# HDMI.net
KiCad netlist of a schematic drawn in Altium Designer
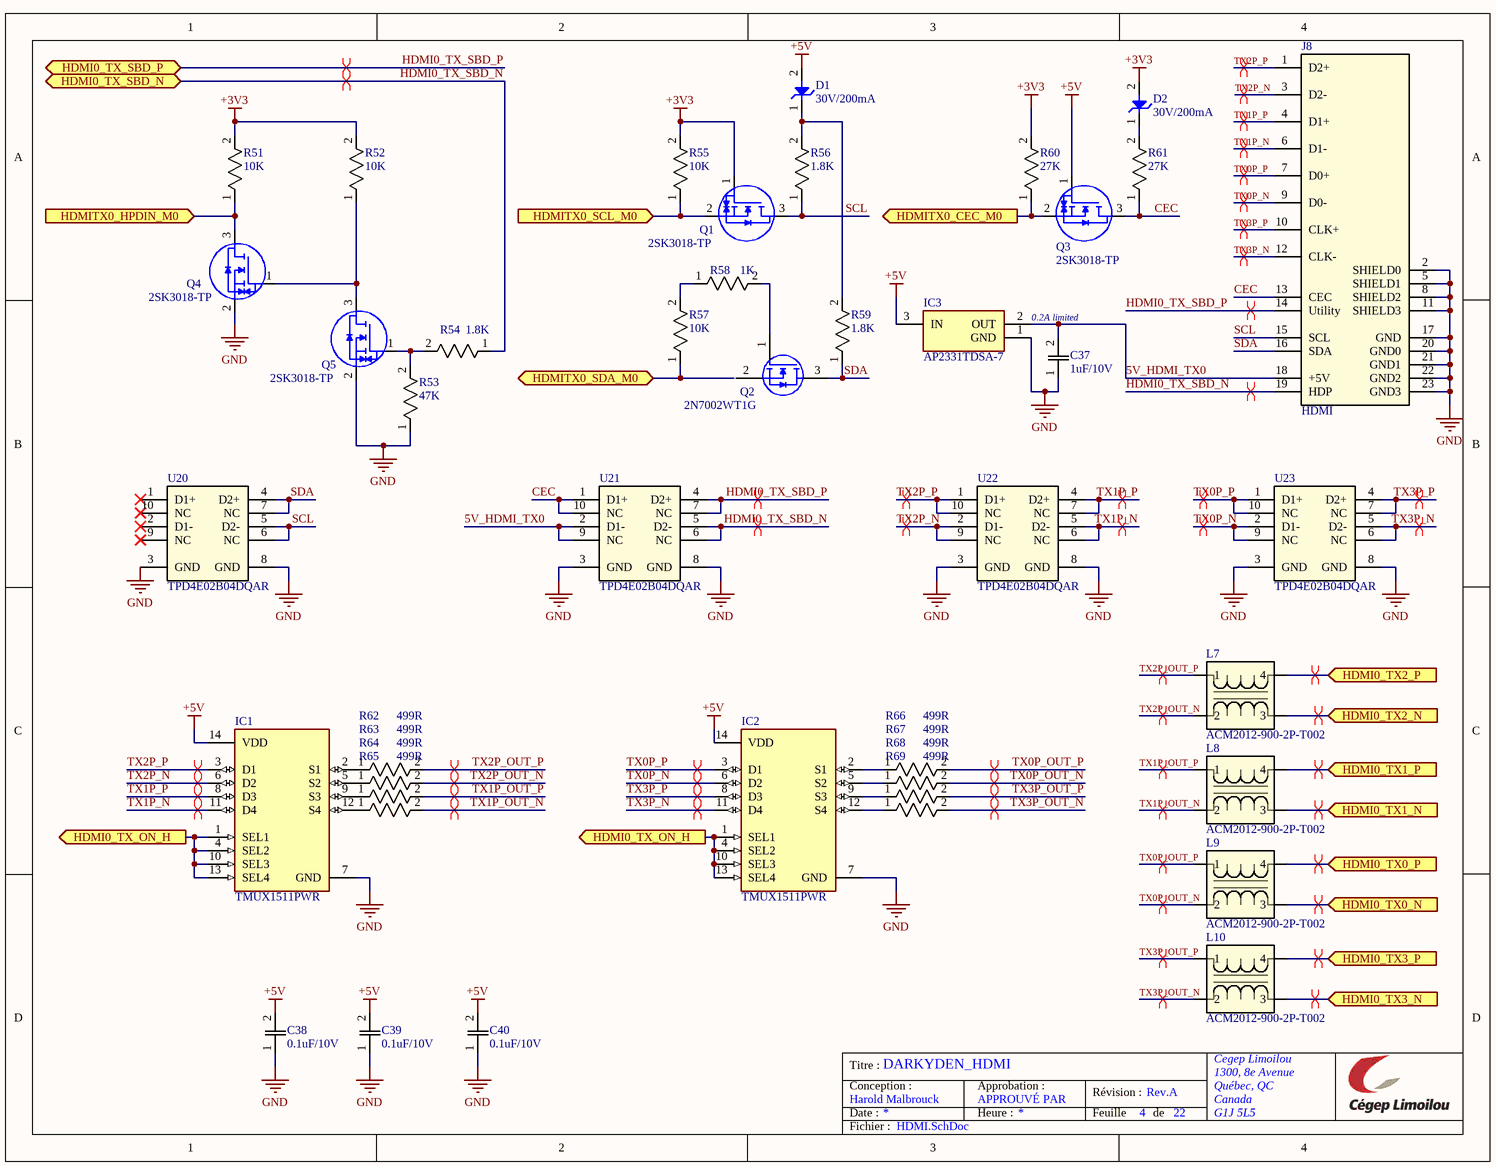
[diagram p0: HDMI.SchDoc]

(export (version "E")
  (design (tool "Eeschema 10.0.6"))
  (components
    (comp (ref "C37")
      (value "1uF/10V")
      (footprint "CAPC220145_88N_KEM")
      (description "Multilayer Ceramic Capacitors MLCC - SMD/SMT 10V 1uF X7R 0805 10%")
      (fields
        (field (name "MANUFACTURER") "KEMET")
        (field (name "MANUFACTURER PART NUMBER") "C0805C105K8RACTU")
      )
      (libsource (lib "C0805C105K8RACTU") (part "C0805C105K8RACTU"))
    )
    (comp (ref "C38")
      (value "0.1uF/10V")
      (footprint "CAPC220145_88N_KEM")
      (description "Cap Ceramic 0.1uF 10V X7R 5% Pad SMD 0805 125C T/R")
      (fields
        (field (name "MANUFACTURER") "KEMET")
        (field (name "MANUFACTURER PART NUMBER") "C0805C104J8RACTU")
      )
      (libsource (lib "C0805C104J8RACTU") (part "C0805C104J8RACTU"))
    )
    (comp (ref "C39")
      (value "0.1uF/10V")
      (footprint "CAPC220145_88N_KEM")
      (description "Cap Ceramic 0.1uF 10V X7R 5% Pad SMD 0805 125C T/R")
      (fields
        (field (name "MANUFACTURER") "KEMET")
        (field (name "MANUFACTURER PART NUMBER") "C0805C104J8RACTU")
      )
      (libsource (lib "C0805C104J8RACTU") (part "C0805C104J8RACTU"))
    )
    (comp (ref "C40")
      (value "0.1uF/10V")
      (footprint "CAPC220145_88N_KEM")
      (description "Cap Ceramic 0.1uF 10V X7R 5% Pad SMD 0805 125C T/R")
      (fields
        (field (name "MANUFACTURER") "KEMET")
        (field (name "MANUFACTURER PART NUMBER") "C0805C104J8RACTU")
      )
      (libsource (lib "C0805C104J8RACTU") (part "C0805C104J8RACTU"))
    )
    (comp (ref "D1")
      (value "30V/200mA")
      (footprint "SamacSys:SODFL1608X70N")
      (description "SCHOTTKY BARRIER DIODE Rectifier Diode, Schottky, 1 Phase, 1 Element, 0.2A, 30V V(RRM), Silicon")
      (fields
        (field (name "MANUFACTURER_PART_NUMBER") "RB521S30T1G")
        (field (name "MOUSER PART NUMBER") "863-RB521S30T1G")
      )
      (libsource (lib "SamacSys") (part "RB521S30T1G"))
    )
    (comp (ref "D2")
      (value "30V/200mA")
      (footprint "SamacSys:SODFL1608X70N")
      (description "SCHOTTKY BARRIER DIODE Rectifier Diode, Schottky, 1 Phase, 1 Element, 0.2A, 30V V(RRM), Silicon")
      (fields
        (field (name "MANUFACTURER_PART_NUMBER") "RB521S30T1G")
        (field (name "MOUSER PART NUMBER") "863-RB521S30T1G")
      )
      (libsource (lib "SamacSys") (part "RB521S30T1G"))
    )
    (comp (ref "IC1")
      (value "TMUX1511PWR")
      (footprint "SamacSys:SOP65P640X120-14N")
      (fields
        (field (name "MOUSER PART NUMBER") "595-TMUX1511PWR")
        (field (name "MANUFACTURER") "Texas Instruments")
      )
      (libsource (lib "SamacSys") (part "TMUX1511PWR"))
    )
    (comp (ref "IC2")
      (value "TMUX1511PWR")
      (footprint "SamacSys:SOP65P640X120-14N")
      (fields
        (field (name "MOUSER PART NUMBER") "595-TMUX1511PWR")
        (field (name "MANUFACTURER") "Texas Instruments")
      )
      (libsource (lib "SamacSys") (part "TMUX1511PWR"))
    )
    (comp (ref "IC3")
      (value "AP2331TDSA-7")
      (footprint "SamacSys:SOT96P240X110-3N")
      (description "USB Power Switch Single 5.2V 0.4A 3-Pin SOT-23 T/R")
      (fields (field (name "MOUSER PART NUMBER") "621-AP2331TDSA-7") (field (name "MANUFACTURER") "Diodes"))
      (libsource (lib "SamacSys") (part "AP2331TDSA-7"))
    )
    (comp (ref "J8")
      (value "HDMI")
      (footprint "CONN19_2001-1-2-21-00-BK_CNC")
      (description "2001-1-2-21-00-BK")
      (libsource (lib "HDMI") (part "HDMI"))
    )
    (comp (ref "L7")
      (value "ACM2012-900-2P-T002")
      (footprint "SamacSys:ACM20129002PT002")
      (description "Ferrite Beads Wirewound Common Mode Filter 90Ohm 100MHz 400mA 0805 T/R")
      (fields (field (name "MOUSER PART NUMBER") "810-ACM20129002PT002") (field (name "MANUFACTURER") "TDK"))
      (libsource (lib "SamacSys") (part "ACM2012-900-2P-T002"))
    )
    (comp (ref "L8")
      (value "ACM2012-900-2P-T002")
      (footprint "SamacSys:ACM20129002PT002")
      (description "Ferrite Beads Wirewound Common Mode Filter 90Ohm 100MHz 400mA 0805 T/R")
      (fields (field (name "MOUSER PART NUMBER") "810-ACM20129002PT002") (field (name "MANUFACTURER") "TDK"))
      (libsource (lib "SamacSys") (part "ACM2012-900-2P-T002"))
    )
    (comp (ref "L9")
      (value "ACM2012-900-2P-T002")
      (footprint "SamacSys:ACM20129002PT002")
      (description "Ferrite Beads Wirewound Common Mode Filter 90Ohm 100MHz 400mA 0805 T/R")
      (fields (field (name "MOUSER PART NUMBER") "810-ACM20129002PT002") (field (name "MANUFACTURER") "TDK"))
      (libsource (lib "SamacSys") (part "ACM2012-900-2P-T002"))
    )
    (comp (ref "L10")
      (value "ACM2012-900-2P-T002")
      (footprint "SamacSys:ACM20129002PT002")
      (description "Ferrite Beads Wirewound Common Mode Filter 90Ohm 100MHz 400mA 0805 T/R")
      (fields (field (name "MOUSER PART NUMBER") "810-ACM20129002PT002") (field (name "MANUFACTURER") "TDK"))
      (libsource (lib "SamacSys") (part "ACM2012-900-2P-T002"))
    )
    (comp (ref "Q1")
      (value "2SK3018-TP")
      (footprint "SamacSys:SOT65P228X120-3N")
      (description "N-Channel 30 V 100mA (Ta) 200mW (Ta) Surface Mount SOT-323")
      (fields (field (name "MOUSER PART NUMBER") "833-2SK3018-TP"))
      (libsource (lib "SamacSys") (part "2SK3018-TP"))
    )
    (comp (ref "Q2")
      (value "2N7002WT1G")
      (footprint "SOT-323-3_2P2X1P35_ONS")
      (description "No Description Available")
      (libsource (lib "2N7002WT1G") (part "2N7002WT1G"))
    )
    (comp (ref "Q3")
      (value "2SK3018-TP")
      (footprint "SamacSys:SOT65P228X120-3N")
      (description "N-Channel 30 V 100mA (Ta) 200mW (Ta) Surface Mount SOT-323")
      (fields (field (name "MOUSER PART NUMBER") "833-2SK3018-TP"))
      (libsource (lib "SamacSys") (part "2SK3018-TP"))
    )
    (comp (ref "Q4")
      (value "2SK3018-TP")
      (footprint "SamacSys:SOT65P228X120-3N")
      (description "N-Channel 30 V 100mA (Ta) 200mW (Ta) Surface Mount SOT-323")
      (fields (field (name "MOUSER PART NUMBER") "833-2SK3018-TP"))
      (libsource (lib "SamacSys") (part "2SK3018-TP"))
    )
    (comp (ref "Q5")
      (value "2SK3018-TP")
      (footprint "SamacSys:SOT65P228X120-3N")
      (description "N-Channel 30 V 100mA (Ta) 200mW (Ta) Surface Mount SOT-323")
      (fields (field (name "MOUSER PART NUMBER") "833-2SK3018-TP"))
      (libsource (lib "SamacSys") (part "2SK3018-TP"))
    )
    (comp (ref "R51")
      (value "10K")
      (footprint "SamacSys:ERJ3EKF1000V")
      (description "10K Ohm 5% Res Thick Film 0603  0.1W(1/10W) ±200ppm/C Pad SMD Automotive T/R")
      (fields
        (field (name "MANUFACTURER_PART_NUMBER") "ERJ-3GEYJ103V")
        (field (name "MOUSER PART NUMBER") "667-ERJ-3GEYJ103V")
      )
      (libsource (lib "SamacSys") (part "ERJ-3GEYJ103V"))
    )
    (comp (ref "R52")
      (value "10K")
      (footprint "SamacSys:ERJ3EKF1000V")
      (description "10K Ohm 5% Res Thick Film 0603  0.1W(1/10W) ±200ppm/C Pad SMD Automotive T/R")
      (fields
        (field (name "MANUFACTURER_PART_NUMBER") "ERJ-3GEYJ103V")
        (field (name "MOUSER PART NUMBER") "667-ERJ-3GEYJ103V")
      )
      (libsource (lib "SamacSys") (part "ERJ-3GEYJ103V"))
    )
    (comp (ref "R53")
      (value "47K")
      (footprint "RC0603N_PAN")
      (description "Resistor Thick Film 0603 47K Ohm 5% 1/10W 200ppm/C Molded SMD Punched Carrier T/R")
      (fields
        (field (name "MANUFACTURER") "Panasonic")
        (field (name "MANUFACTURER PART NUMBER") "ERJ-3GEYJ473V")
      )
      (libsource (lib "ERJ-3GEYJ473V") (part "ERJ-3GEYJ473V"))
    )
    (comp (ref "R54")
      (value "1.8K")
      (footprint "RC0603N_PAN")
      (description "SMD Chip Resistor, 1.8 kOhm, ± 5%, 100 mW, 0603 [1608 Metric], Thick Film, General Purpose")
      (fields
        (field (name "MANUFACTURER") "Panasonic")
        (field (name "MANUFACTURER PART NUMBER") "ERJ-3GEYJ182V")
      )
      (libsource (lib "ERJ-3GEYJ182V") (part "ERJ-3GEYJ182V"))
    )
    (comp (ref "R55")
      (value "10K")
      (footprint "SamacSys:ERJ3EKF1000V")
      (description "10K Ohm 5% Res Thick Film 0603  0.1W(1/10W) ±200ppm/C Pad SMD Automotive T/R")
      (fields
        (field (name "MANUFACTURER_PART_NUMBER") "ERJ-3GEYJ103V")
        (field (name "MOUSER PART NUMBER") "667-ERJ-3GEYJ103V")
      )
      (libsource (lib "SamacSys") (part "ERJ-3GEYJ103V"))
    )
    (comp (ref "R56")
      (value "1.8K")
      (footprint "RC0603N_PAN")
      (description "SMD Chip Resistor, 1.8 kOhm, ± 5%, 100 mW, 0603 [1608 Metric], Thick Film, General Purpose")
      (fields
        (field (name "MANUFACTURER") "Panasonic")
        (field (name "MANUFACTURER PART NUMBER") "ERJ-3GEYJ182V")
      )
      (libsource (lib "ERJ-3GEYJ182V") (part "ERJ-3GEYJ182V"))
    )
    (comp (ref "R57")
      (value "10K")
      (footprint "SamacSys:ERJ3EKF1000V")
      (description "10K Ohm 5% Res Thick Film 0603  0.1W(1/10W) ±200ppm/C Pad SMD Automotive T/R")
      (fields
        (field (name "MANUFACTURER_PART_NUMBER") "ERJ-3GEYJ103V")
        (field (name "MOUSER PART NUMBER") "667-ERJ-3GEYJ103V")
      )
      (libsource (lib "SamacSys") (part "ERJ-3GEYJ103V"))
    )
    (comp (ref "R58")
      (value "1K")
      (footprint "SamacSys:RESC1608X55N")
      (description "1K Ohm 1% 1/10W Res Thick Film 0603 ±100ppm/°C Molded SMD Punched Carrier T/R")
      (fields
        (field (name "MANUFACTURER_PART_NUMBER") "ERJ-3EKF1001V")
        (field (name "MOUSER PART NUMBER") "667-ERJ-3EKF1001V")
      )
      (libsource (lib "SamacSys") (part "ERJ-3EKF1001V"))
    )
    (comp (ref "R59")
      (value "1.8K")
      (footprint "RC0603N_PAN")
      (description "SMD Chip Resistor, 1.8 kOhm, ± 5%, 100 mW, 0603 [1608 Metric], Thick Film, General Purpose")
      (fields
        (field (name "MANUFACTURER") "Panasonic")
        (field (name "MANUFACTURER PART NUMBER") "ERJ-3GEYJ182V")
      )
      (libsource (lib "ERJ-3GEYJ182V") (part "ERJ-3GEYJ182V"))
    )
    (comp (ref "R60")
      (value "27K")
      (footprint "RC0603N_PAN")
      (description "Res Thick Film 0603 27K Ohm 1% 1/10W ±100ppm/°C Molded SMD Punched Carrier T/R")
      (fields
        (field (name "MANUFACTURER") "Panasonic")
        (field (name "MANUFACTURER PART NUMBER") "ERJ-3EKF2702V")
      )
      (libsource (lib "ERJ-3EKF2702V") (part "ERJ-3EKF2702V"))
    )
    (comp (ref "R61")
      (value "27K")
      (footprint "RC0603N_PAN")
      (description "Res Thick Film 0603 27K Ohm 1% 1/10W ±100ppm/°C Molded SMD Punched Carrier T/R")
      (fields
        (field (name "MANUFACTURER") "Panasonic")
        (field (name "MANUFACTURER PART NUMBER") "ERJ-3EKF2702V")
      )
      (libsource (lib "ERJ-3EKF2702V") (part "ERJ-3EKF2702V"))
    )
    (comp (ref "R62")
      (value "499R")
      (footprint "RC0603N_PAN")
      (description "SMD Chip Resistor, 499 Ohm, ï¿½ 1%, 100 mW, 0603 [1608 Metric], Thick Film, Precision")
      (fields
        (field (name "MANUFACTURER") "Panasonic")
        (field (name "MANUFACTURER PART NUMBER") "ERJ-3EKF4990V")
      )
      (libsource (lib "ERJ-3EKF4990V") (part "ERJ-3EKF4990V"))
    )
    (comp (ref "R63")
      (value "499R")
      (footprint "RC0603N_PAN")
      (description "SMD Chip Resistor, 499 Ohm, ï¿½ 1%, 100 mW, 0603 [1608 Metric], Thick Film, Precision")
      (fields
        (field (name "MANUFACTURER") "Panasonic")
        (field (name "MANUFACTURER PART NUMBER") "ERJ-3EKF4990V")
      )
      (libsource (lib "ERJ-3EKF4990V") (part "ERJ-3EKF4990V"))
    )
    (comp (ref "R64")
      (value "499R")
      (footprint "RC0603N_PAN")
      (description "SMD Chip Resistor, 499 Ohm, ï¿½ 1%, 100 mW, 0603 [1608 Metric], Thick Film, Precision")
      (fields
        (field (name "MANUFACTURER") "Panasonic")
        (field (name "MANUFACTURER PART NUMBER") "ERJ-3EKF4990V")
      )
      (libsource (lib "ERJ-3EKF4990V") (part "ERJ-3EKF4990V"))
    )
    (comp (ref "R65")
      (value "499R")
      (footprint "RC0603N_PAN")
      (description "SMD Chip Resistor, 499 Ohm, ï¿½ 1%, 100 mW, 0603 [1608 Metric], Thick Film, Precision")
      (fields
        (field (name "MANUFACTURER") "Panasonic")
        (field (name "MANUFACTURER PART NUMBER") "ERJ-3EKF4990V")
      )
      (libsource (lib "ERJ-3EKF4990V") (part "ERJ-3EKF4990V"))
    )
    (comp (ref "R66")
      (value "499R")
      (footprint "RC0603N_PAN")
      (description "SMD Chip Resistor, 499 Ohm, ï¿½ 1%, 100 mW, 0603 [1608 Metric], Thick Film, Precision")
      (fields
        (field (name "MANUFACTURER") "Panasonic")
        (field (name "MANUFACTURER PART NUMBER") "ERJ-3EKF4990V")
      )
      (libsource (lib "ERJ-3EKF4990V") (part "ERJ-3EKF4990V"))
    )
    (comp (ref "R67")
      (value "499R")
      (footprint "RC0603N_PAN")
      (description "SMD Chip Resistor, 499 Ohm, ï¿½ 1%, 100 mW, 0603 [1608 Metric], Thick Film, Precision")
      (fields
        (field (name "MANUFACTURER") "Panasonic")
        (field (name "MANUFACTURER PART NUMBER") "ERJ-3EKF4990V")
      )
      (libsource (lib "ERJ-3EKF4990V") (part "ERJ-3EKF4990V"))
    )
    (comp (ref "R68")
      (value "499R")
      (footprint "RC0603N_PAN")
      (description "SMD Chip Resistor, 499 Ohm, ï¿½ 1%, 100 mW, 0603 [1608 Metric], Thick Film, Precision")
      (fields
        (field (name "MANUFACTURER") "Panasonic")
        (field (name "MANUFACTURER PART NUMBER") "ERJ-3EKF4990V")
      )
      (libsource (lib "ERJ-3EKF4990V") (part "ERJ-3EKF4990V"))
    )
    (comp (ref "R69")
      (value "499R")
      (footprint "RC0603N_PAN")
      (description "SMD Chip Resistor, 499 Ohm, ï¿½ 1%, 100 mW, 0603 [1608 Metric], Thick Film, Precision")
      (fields
        (field (name "MANUFACTURER") "Panasonic")
        (field (name "MANUFACTURER PART NUMBER") "ERJ-3EKF4990V")
      )
      (libsource (lib "ERJ-3EKF4990V") (part "ERJ-3EKF4990V"))
    )
    (comp (ref "U20")
      (value "TPD4E02B04DQAR")
      (footprint "DQA0010A")
      (description "TVS DIODE 3.6V 8.8V 10USON / 4-Channel ESD Protection Diode for USB Type-C and HDMI 2.0")
      (fields (field (name "MANUFACTURER") "Texas Instruments"))
      (libsource (lib "TPD4E02B04DQAR") (part "TPD4E02B04DQAR"))
    )
    (comp (ref "U21")
      (value "TPD4E02B04DQAR")
      (footprint "DQA0010A")
      (description "TVS DIODE 3.6V 8.8V 10USON / 4-Channel ESD Protection Diode for USB Type-C and HDMI 2.0")
      (fields (field (name "MANUFACTURER") "Texas Instruments"))
      (libsource (lib "TPD4E02B04DQAR") (part "TPD4E02B04DQAR"))
    )
    (comp (ref "U22")
      (value "TPD4E02B04DQAR")
      (footprint "DQA0010A")
      (description "TVS DIODE 3.6V 8.8V 10USON / 4-Channel ESD Protection Diode for USB Type-C and HDMI 2.0")
      (fields (field (name "MANUFACTURER") "Texas Instruments"))
      (libsource (lib "TPD4E02B04DQAR") (part "TPD4E02B04DQAR"))
    )
    (comp (ref "U23")
      (value "TPD4E02B04DQAR")
      (footprint "DQA0010A")
      (description "TVS DIODE 3.6V 8.8V 10USON / 4-Channel ESD Protection Diode for USB Type-C and HDMI 2.0")
      (fields (field (name "MANUFACTURER") "Texas Instruments"))
      (libsource (lib "TPD4E02B04DQAR") (part "TPD4E02B04DQAR"))
    )
  )
  (nets
    (net (code "1") (name "+3V3") (class "Default")
      (node (ref "D2") (pin "2") (pinfunction "A_2") (pintype "passive"))
      (node (ref "Q1") (pin "1") (pinfunction "G_1") (pintype "passive"))
      (node (ref "R51") (pin "2") (pinfunction "2_2") (pintype "passive"))
      (node (ref "R52") (pin "2") (pinfunction "2_2") (pintype "passive"))
      (node (ref "R55") (pin "2") (pinfunction "2_2") (pintype "passive"))
      (node (ref "R60") (pin "2") (pinfunction "2_2") (pintype "passive"))
    )
    (net (code "2") (name "+5V") (class "Default")
      (node (ref "C38") (pin "2") (pinfunction "2_2") (pintype "passive"))
      (node (ref "C39") (pin "2") (pinfunction "2_2") (pintype "passive"))
      (node (ref "C40") (pin "2") (pinfunction "2_2") (pintype "passive"))
      (node (ref "D1") (pin "2") (pinfunction "A_2") (pintype "passive"))
      (node (ref "IC1") (pin "14") (pinfunction "VDD_14") (pintype "power_in"))
      (node (ref "IC2") (pin "14") (pinfunction "VDD_14") (pintype "power_in"))
      (node (ref "IC3") (pin "3") (pinfunction "IN_3") (pintype "passive"))
      (node (ref "Q3") (pin "1") (pinfunction "G_1") (pintype "passive"))
    )
    (net (code "3") (name "/5V_HDMI_TX0") (class "Default")
      (node (ref "C37") (pin "2") (pinfunction "2_2") (pintype "passive"))
      (node (ref "IC3") (pin "2") (pinfunction "OUT_2") (pintype "passive"))
      (node (ref "J8") (pin "18") (pinfunction "+5V_18") (pintype "passive"))
      (node (ref "U21") (pin "2") (pinfunction "D1-_2") (pintype "passive"))
      (node (ref "U21") (pin "9") (pinfunction "NC_9") (pintype "passive"))
    )
    (net (code "4") (name "/CEC") (class "Default")
      (node (ref "J8") (pin "13") (pinfunction "CEC_13") (pintype "passive"))
      (node (ref "Q3") (pin "3") (pinfunction "D_3") (pintype "passive"))
      (node (ref "R61") (pin "1") (pinfunction "1_1") (pintype "passive"))
      (node (ref "U21") (pin "1") (pinfunction "D1+_1") (pintype "passive"))
      (node (ref "U21") (pin "10") (pinfunction "NC_10") (pintype "passive"))
    )
    (net (code "5") (name "/HDMI0_TX0_N") (class "Default")
      (node (ref "L9") (pin "3") (pinfunction "3_3") (pintype "passive"))
    )
    (net (code "6") (name "/HDMI0_TX0_P") (class "Default")
      (node (ref "L9") (pin "4") (pinfunction "4_4") (pintype "passive"))
    )
    (net (code "7") (name "/HDMI0_TX1_N") (class "Default")
      (node (ref "L8") (pin "3") (pinfunction "3_3") (pintype "passive"))
    )
    (net (code "8") (name "/HDMI0_TX1_P") (class "Default")
      (node (ref "L8") (pin "4") (pinfunction "4_4") (pintype "passive"))
    )
    (net (code "9") (name "/HDMI0_TX2_N") (class "Default")
      (node (ref "L7") (pin "3") (pinfunction "3_3") (pintype "passive"))
    )
    (net (code "10") (name "/HDMI0_TX2_P") (class "Default")
      (node (ref "L7") (pin "4") (pinfunction "4_4") (pintype "passive"))
    )
    (net (code "11") (name "/HDMI0_TX3_N") (class "Default")
      (node (ref "L10") (pin "3") (pinfunction "3_3") (pintype "passive"))
    )
    (net (code "12") (name "/HDMI0_TX3_P") (class "Default")
      (node (ref "L10") (pin "4") (pinfunction "4_4") (pintype "passive"))
    )
    (net (code "13") (name "/HDMI0_TX_ON_H") (class "Default")
      (node (ref "IC1") (pin "1") (pinfunction "SEL1_1") (pintype "input"))
      (node (ref "IC1") (pin "10") (pinfunction "SEL3_10") (pintype "input"))
      (node (ref "IC1") (pin "13") (pinfunction "SEL4_13") (pintype "input"))
      (node (ref "IC1") (pin "4") (pinfunction "SEL2_4") (pintype "input"))
      (node (ref "IC2") (pin "1") (pinfunction "SEL1_1") (pintype "input"))
      (node (ref "IC2") (pin "10") (pinfunction "SEL3_10") (pintype "input"))
      (node (ref "IC2") (pin "13") (pinfunction "SEL4_13") (pintype "input"))
      (node (ref "IC2") (pin "4") (pinfunction "SEL2_4") (pintype "input"))
    )
    (net (code "14") (name "/HDMI0_TX_SBD_N") (class "Default")
      (node (ref "J8") (pin "19") (pinfunction "HDP_19") (pintype "passive"))
      (node (ref "R54") (pin "1") (pinfunction "1_1") (pintype "passive"))
      (node (ref "U21") (pin "5") (pinfunction "D2-_5") (pintype "passive"))
      (node (ref "U21") (pin "6") (pinfunction "NC_6") (pintype "passive"))
    )
    (net (code "15") (name "/HDMI0_TX_SBD_P") (class "Default")
      (node (ref "J8") (pin "14") (pinfunction "Utility_14") (pintype "passive"))
      (node (ref "U21") (pin "4") (pinfunction "D2+_4") (pintype "passive"))
      (node (ref "U21") (pin "7") (pinfunction "NC_7") (pintype "passive"))
    )
    (net (code "16") (name "/HDMITX0_CEC_M0") (class "Default")
      (node (ref "Q3") (pin "2") (pinfunction "S_2") (pintype "passive"))
      (node (ref "R60") (pin "1") (pinfunction "1_1") (pintype "passive"))
    )
    (net (code "17") (name "/HDMITX0_HPDIN_M0") (class "Default")
      (node (ref "Q4") (pin "3") (pinfunction "D_3") (pintype "passive"))
      (node (ref "R51") (pin "1") (pinfunction "1_1") (pintype "passive"))
    )
    (net (code "18") (name "/HDMITX0_SCL_M0") (class "Default")
      (node (ref "Q1") (pin "2") (pinfunction "S_2") (pintype "passive"))
      (node (ref "R55") (pin "1") (pinfunction "1_1") (pintype "passive"))
    )
    (net (code "19") (name "/HDMITX0_SDA_M0") (class "Default")
      (node (ref "R57") (pin "1") (pinfunction "1_1") (pintype "passive"))
    )
    (net (code "20") (name "/SCL") (class "Default")
      (node (ref "J8") (pin "15") (pinfunction "SCL_15") (pintype "passive"))
      (node (ref "Q1") (pin "3") (pinfunction "D_3") (pintype "passive"))
      (node (ref "R56") (pin "1") (pinfunction "1_1") (pintype "passive"))
      (node (ref "U20") (pin "5") (pinfunction "D2-_5") (pintype "passive"))
      (node (ref "U20") (pin "6") (pinfunction "NC_6") (pintype "passive"))
    )
    (net (code "21") (name "/SDA") (class "Default")
      (node (ref "J8") (pin "16") (pinfunction "SDA_16") (pintype "passive"))
      (node (ref "Q2") (pin "3") (pinfunction "DRAIN_3") (pintype "passive"))
      (node (ref "R59") (pin "1") (pinfunction "1_1") (pintype "passive"))
      (node (ref "U20") (pin "4") (pinfunction "D2+_4") (pintype "passive"))
      (node (ref "U20") (pin "7") (pinfunction "NC_7") (pintype "passive"))
    )
    (net (code "22") (name "/TX0P_N") (class "Default")
      (node (ref "IC2") (pin "6") (pinfunction "D2_6") (pintype "bidirectional"))
      (node (ref "J8") (pin "9") (pinfunction "D0-_9") (pintype "passive"))
      (node (ref "U23") (pin "2") (pinfunction "D1-_2") (pintype "passive"))
      (node (ref "U23") (pin "9") (pinfunction "NC_9") (pintype "passive"))
    )
    (net (code "23") (name "/TX0P_OUT_N") (class "Default")
      (node (ref "L9") (pin "2") (pinfunction "2_2") (pintype "passive"))
      (node (ref "R67") (pin "2") (pinfunction "2_2") (pintype "passive"))
    )
    (net (code "24") (name "/TX0P_OUT_P") (class "Default")
      (node (ref "L9") (pin "1") (pinfunction "1_1") (pintype "passive"))
      (node (ref "R66") (pin "2") (pinfunction "2_2") (pintype "passive"))
    )
    (net (code "25") (name "/TX0P_P") (class "Default")
      (node (ref "IC2") (pin "3") (pinfunction "D1_3") (pintype "bidirectional"))
      (node (ref "J8") (pin "7") (pinfunction "D0+_7") (pintype "passive"))
      (node (ref "U23") (pin "1") (pinfunction "D1+_1") (pintype "passive"))
      (node (ref "U23") (pin "10") (pinfunction "NC_10") (pintype "passive"))
    )
    (net (code "26") (name "/TX1P_N") (class "Default")
      (node (ref "IC1") (pin "11") (pinfunction "D4_11") (pintype "bidirectional"))
      (node (ref "J8") (pin "6") (pinfunction "D1-_6") (pintype "passive"))
      (node (ref "U22") (pin "5") (pinfunction "D2-_5") (pintype "passive"))
      (node (ref "U22") (pin "6") (pinfunction "NC_6") (pintype "passive"))
    )
    (net (code "27") (name "/TX1P_OUT_N") (class "Default")
      (node (ref "L8") (pin "2") (pinfunction "2_2") (pintype "passive"))
      (node (ref "R65") (pin "2") (pinfunction "2_2") (pintype "passive"))
    )
    (net (code "28") (name "/TX1P_OUT_P") (class "Default")
      (node (ref "L8") (pin "1") (pinfunction "1_1") (pintype "passive"))
      (node (ref "R64") (pin "2") (pinfunction "2_2") (pintype "passive"))
    )
    (net (code "29") (name "/TX1P_P") (class "Default")
      (node (ref "IC1") (pin "8") (pinfunction "D3_8") (pintype "bidirectional"))
      (node (ref "J8") (pin "4") (pinfunction "D1+_4") (pintype "passive"))
      (node (ref "U22") (pin "4") (pinfunction "D2+_4") (pintype "passive"))
      (node (ref "U22") (pin "7") (pinfunction "NC_7") (pintype "passive"))
    )
    (net (code "30") (name "/TX2P_N") (class "Default")
      (node (ref "IC1") (pin "6") (pinfunction "D2_6") (pintype "bidirectional"))
      (node (ref "J8") (pin "3") (pinfunction "D2-_3") (pintype "passive"))
      (node (ref "U22") (pin "2") (pinfunction "D1-_2") (pintype "passive"))
      (node (ref "U22") (pin "9") (pinfunction "NC_9") (pintype "passive"))
    )
    (net (code "31") (name "/TX2P_OUT_N") (class "Default")
      (node (ref "L7") (pin "2") (pinfunction "2_2") (pintype "passive"))
      (node (ref "R63") (pin "2") (pinfunction "2_2") (pintype "passive"))
    )
    (net (code "32") (name "/TX2P_OUT_P") (class "Default")
      (node (ref "L7") (pin "1") (pinfunction "1_1") (pintype "passive"))
      (node (ref "R62") (pin "2") (pinfunction "2_2") (pintype "passive"))
    )
    (net (code "33") (name "/TX2P_P") (class "Default")
      (node (ref "IC1") (pin "3") (pinfunction "D1_3") (pintype "bidirectional"))
      (node (ref "J8") (pin "1") (pinfunction "D2+_1") (pintype "passive"))
      (node (ref "U22") (pin "1") (pinfunction "D1+_1") (pintype "passive"))
      (node (ref "U22") (pin "10") (pinfunction "NC_10") (pintype "passive"))
    )
    (net (code "34") (name "/TX3P_N") (class "Default")
      (node (ref "IC2") (pin "11") (pinfunction "D4_11") (pintype "bidirectional"))
      (node (ref "J8") (pin "12") (pinfunction "CLK-_12") (pintype "passive"))
      (node (ref "U23") (pin "5") (pinfunction "D2-_5") (pintype "passive"))
      (node (ref "U23") (pin "6") (pinfunction "NC_6") (pintype "passive"))
    )
    (net (code "35") (name "/TX3P_OUT_N") (class "Default")
      (node (ref "L10") (pin "2") (pinfunction "2_2") (pintype "passive"))
      (node (ref "R69") (pin "2") (pinfunction "2_2") (pintype "passive"))
    )
    (net (code "36") (name "/TX3P_OUT_P") (class "Default")
      (node (ref "L10") (pin "1") (pinfunction "1_1") (pintype "passive"))
      (node (ref "R68") (pin "2") (pinfunction "2_2") (pintype "passive"))
    )
    (net (code "37") (name "/TX3P_P") (class "Default")
      (node (ref "IC2") (pin "8") (pinfunction "D3_8") (pintype "bidirectional"))
      (node (ref "J8") (pin "10") (pinfunction "CLK+_10") (pintype "passive"))
      (node (ref "U23") (pin "4") (pinfunction "D2+_4") (pintype "passive"))
      (node (ref "U23") (pin "7") (pinfunction "NC_7") (pintype "passive"))
    )
    (net (code "38") (name "GND") (class "Default")
      (node (ref "C37") (pin "1") (pinfunction "1_1") (pintype "passive"))
      (node (ref "C38") (pin "1") (pinfunction "1_1") (pintype "passive"))
      (node (ref "C39") (pin "1") (pinfunction "1_1") (pintype "passive"))
      (node (ref "C40") (pin "1") (pinfunction "1_1") (pintype "passive"))
      (node (ref "IC1") (pin "7") (pinfunction "GND_7") (pintype "power_in"))
      (node (ref "IC2") (pin "7") (pinfunction "GND_7") (pintype "power_in"))
      (node (ref "IC3") (pin "1") (pinfunction "GND_1") (pintype "passive"))
      (node (ref "J8") (pin "11") (pinfunction "SHIELD3_11") (pintype "passive"))
      (node (ref "J8") (pin "17") (pinfunction "GND_17") (pintype "passive"))
      (node (ref "J8") (pin "2") (pinfunction "SHIELD0_2") (pintype "passive"))
      (node (ref "J8") (pin "20") (pinfunction "GND0_20") (pintype "passive"))
      (node (ref "J8") (pin "21") (pinfunction "GND1_21") (pintype "passive"))
      (node (ref "J8") (pin "22") (pinfunction "GND2_22") (pintype "passive"))
      (node (ref "J8") (pin "23") (pinfunction "GND3_23") (pintype "passive"))
      (node (ref "J8") (pin "5") (pinfunction "SHIELD1_5") (pintype "passive"))
      (node (ref "J8") (pin "8") (pinfunction "SHIELD2_8") (pintype "passive"))
      (node (ref "Q4") (pin "2") (pinfunction "S_2") (pintype "passive"))
      (node (ref "Q5") (pin "2") (pinfunction "S_2") (pintype "passive"))
      (node (ref "R53") (pin "1") (pinfunction "1_1") (pintype "passive"))
      (node (ref "U20") (pin "3") (pinfunction "GND_3") (pintype "passive"))
      (node (ref "U20") (pin "8") (pinfunction "GND_8") (pintype "passive"))
      (node (ref "U21") (pin "3") (pinfunction "GND_3") (pintype "passive"))
      (node (ref "U21") (pin "8") (pinfunction "GND_8") (pintype "passive"))
      (node (ref "U22") (pin "3") (pinfunction "GND_3") (pintype "passive"))
      (node (ref "U22") (pin "8") (pinfunction "GND_8") (pintype "passive"))
      (node (ref "U23") (pin "3") (pinfunction "GND_3") (pintype "passive"))
      (node (ref "U23") (pin "8") (pinfunction "GND_8") (pintype "passive"))
    )
    (net (code "39") (name "Net-(D1-K)") (class "Default")
      (node (ref "D1") (pin "1") (pinfunction "K_1") (pintype "passive"))
      (node (ref "R56") (pin "2") (pinfunction "2_2") (pintype "passive"))
      (node (ref "R59") (pin "2") (pinfunction "2_2") (pintype "passive"))
    )
    (net (code "40") (name "Net-(D2-K)") (class "Default")
      (node (ref "D2") (pin "1") (pinfunction "K_1") (pintype "passive"))
      (node (ref "R61") (pin "2") (pinfunction "2_2") (pintype "passive"))
    )
    (net (code "41") (name "Net-(IC1-S1)") (class "Default")
      (node (ref "IC1") (pin "2") (pinfunction "S1_2") (pintype "bidirectional"))
      (node (ref "R62") (pin "1") (pinfunction "1_1") (pintype "passive"))
    )
    (net (code "42") (name "Net-(IC1-S2)") (class "Default")
      (node (ref "IC1") (pin "5") (pinfunction "S2_5") (pintype "bidirectional"))
      (node (ref "R63") (pin "1") (pinfunction "1_1") (pintype "passive"))
    )
    (net (code "43") (name "Net-(IC1-S3)") (class "Default")
      (node (ref "IC1") (pin "9") (pinfunction "S3_9") (pintype "bidirectional"))
      (node (ref "R64") (pin "1") (pinfunction "1_1") (pintype "passive"))
    )
    (net (code "44") (name "Net-(IC1-S4)") (class "Default")
      (node (ref "IC1") (pin "12") (pinfunction "S4_12") (pintype "bidirectional"))
      (node (ref "R65") (pin "1") (pinfunction "1_1") (pintype "passive"))
    )
    (net (code "45") (name "Net-(IC2-S1)") (class "Default")
      (node (ref "IC2") (pin "2") (pinfunction "S1_2") (pintype "bidirectional"))
      (node (ref "R66") (pin "1") (pinfunction "1_1") (pintype "passive"))
    )
    (net (code "46") (name "Net-(IC2-S2)") (class "Default")
      (node (ref "IC2") (pin "5") (pinfunction "S2_5") (pintype "bidirectional"))
      (node (ref "R67") (pin "1") (pinfunction "1_1") (pintype "passive"))
    )
    (net (code "47") (name "Net-(IC2-S3)") (class "Default")
      (node (ref "IC2") (pin "9") (pinfunction "S3_9") (pintype "bidirectional"))
      (node (ref "R68") (pin "1") (pinfunction "1_1") (pintype "passive"))
    )
    (net (code "48") (name "Net-(IC2-S4)") (class "Default")
      (node (ref "IC2") (pin "12") (pinfunction "S4_12") (pintype "bidirectional"))
      (node (ref "R69") (pin "1") (pinfunction "1_1") (pintype "passive"))
    )
    (net (code "49") (name "Net-(Q2-GATE)") (class "Default")
      (node (ref "Q2") (pin "1") (pinfunction "GATE_1") (pintype "passive"))
      (node (ref "R58") (pin "2") (pinfunction "2_2") (pintype "passive"))
    )
    (net (code "50") (name "Net-(Q4-G)") (class "Default")
      (node (ref "Q4") (pin "1") (pinfunction "G_1") (pintype "passive"))
      (node (ref "Q5") (pin "3") (pinfunction "D_3") (pintype "passive"))
      (node (ref "R52") (pin "1") (pinfunction "1_1") (pintype "passive"))
    )
    (net (code "51") (name "Net-(Q5-G)") (class "Default")
      (node (ref "Q5") (pin "1") (pinfunction "G_1") (pintype "passive"))
      (node (ref "R53") (pin "2") (pinfunction "2_2") (pintype "passive"))
      (node (ref "R54") (pin "2") (pinfunction "2_2") (pintype "passive"))
    )
    (net (code "52") (name "Net-(R57-Pad2)") (class "Default")
      (node (ref "R57") (pin "2") (pinfunction "2_2") (pintype "passive"))
      (node (ref "R58") (pin "1") (pinfunction "1_1") (pintype "passive"))
    )
    (net (code "53") (name "unconnected-(Q2-SOURCE-Pad2)") (class "Default")
      (node (ref "Q2") (pin "2") (pinfunction "SOURCE_2") (pintype "passive"))
    )
    (net (code "54") (name "unconnected-(U20-D1+-Pad1)") (class "Default")
      (node (ref "U20") (pin "1") (pinfunction "D1+_1") (pintype "passive+no_connect"))
    )
    (net (code "55") (name "unconnected-(U20-D1--Pad2)") (class "Default")
      (node (ref "U20") (pin "2") (pinfunction "D1-_2") (pintype "passive+no_connect"))
    )
    (net (code "56") (name "unconnected-(U20-NC-Pad9)") (class "Default")
      (node (ref "U20") (pin "9") (pinfunction "NC_9") (pintype "passive+no_connect"))
    )
    (net (code "57") (name "unconnected-(U20-NC-Pad10)") (class "Default")
      (node (ref "U20") (pin "10") (pinfunction "NC_10") (pintype "passive+no_connect"))
    )
  )
)
